# scaremin.net
KiCad netlist of a schematic drawn in EAGLE
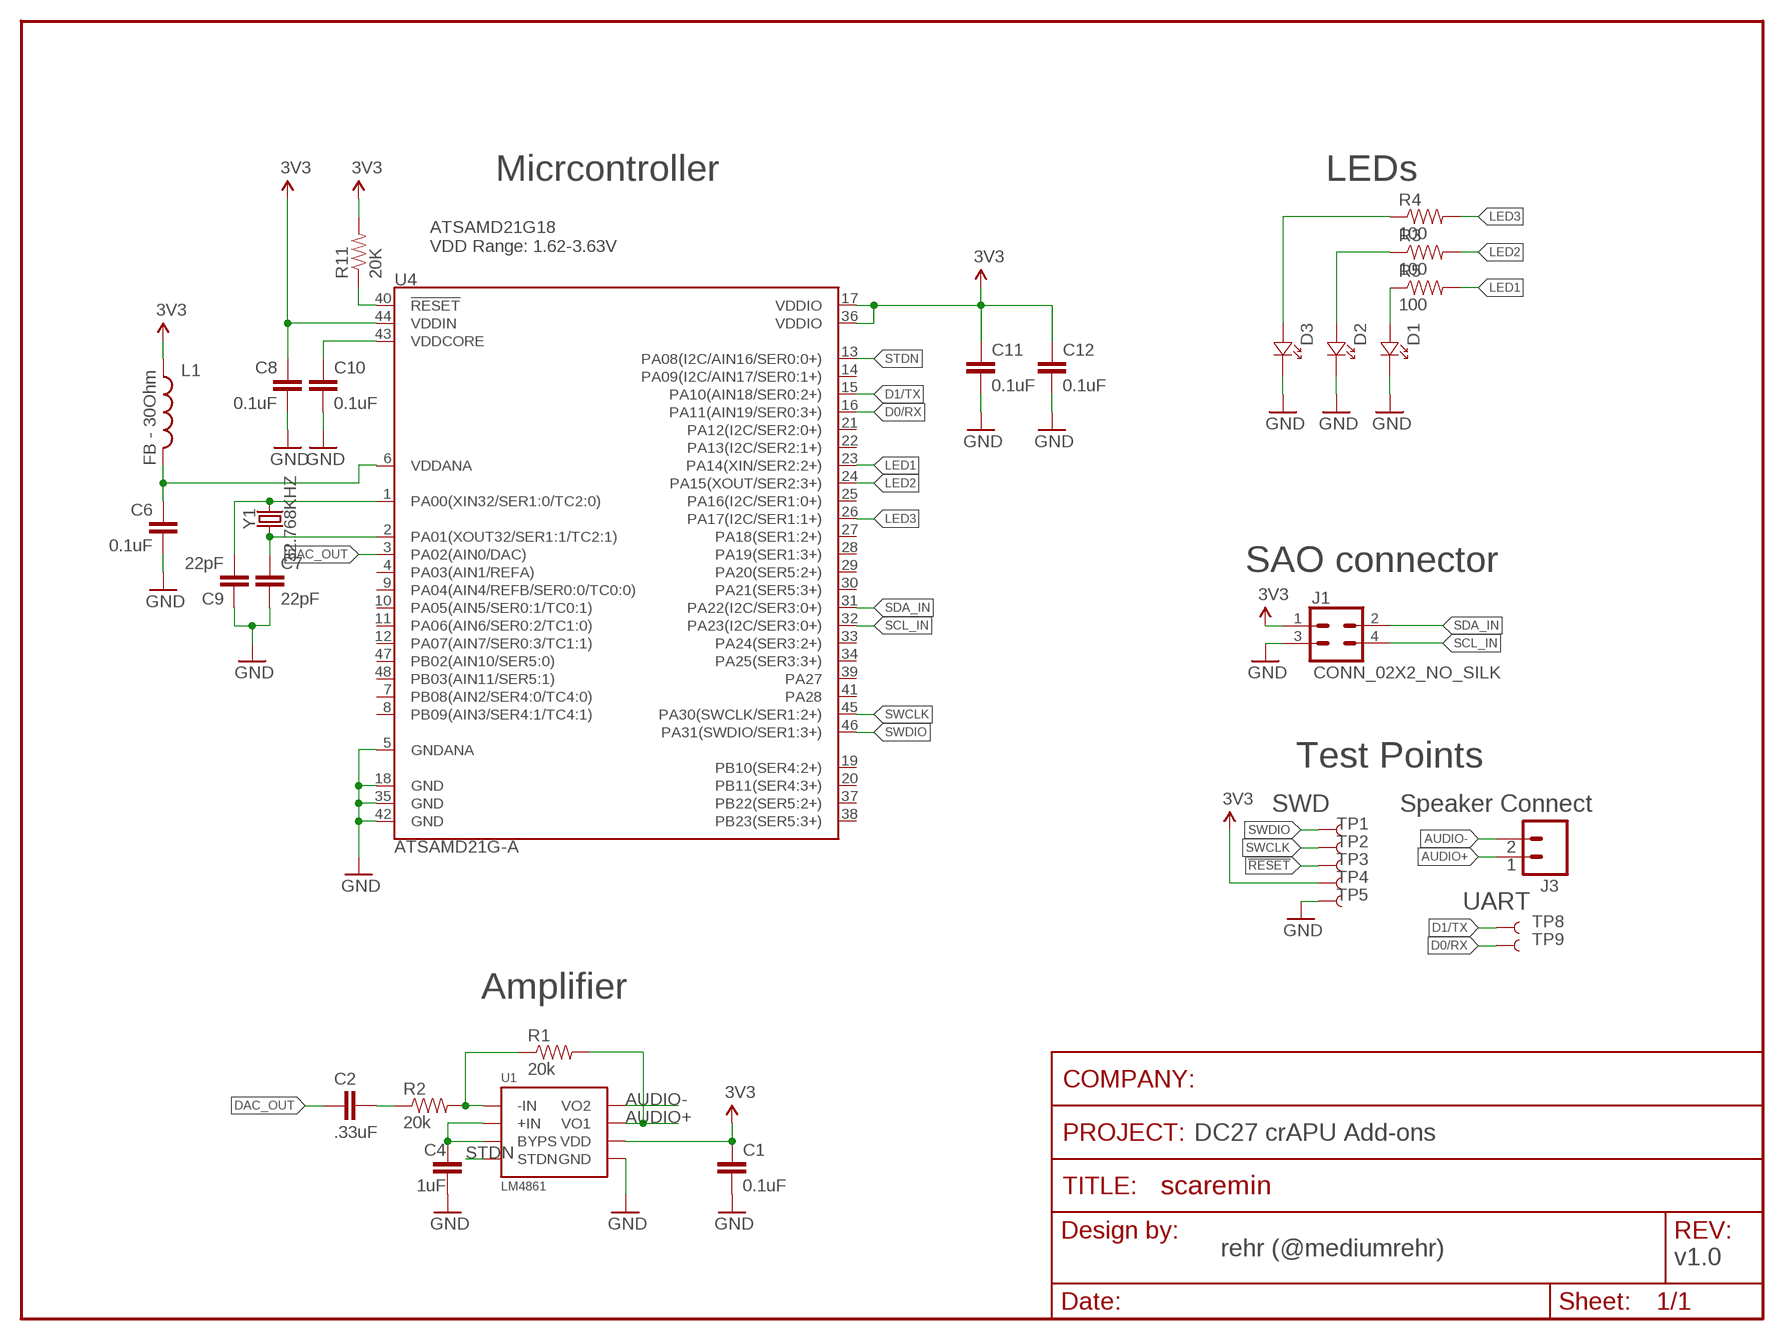
[diagram p0: schematic, sheet 1]

(export (version "E")
  (design (tool "Eeschema 10.0.6"))
  (components
    (comp (ref "C1")
      (value "0.1uF")
      (footprint "eagle-import:0603-CAP")
      (libsource (lib "eagle-import") (part "CAP0603-CAP"))
    )
    (comp (ref "C2")
      (value ".33uF")
      (footprint "eagle-import:0603-CAP")
      (libsource (lib "eagle-import") (part "CAP0603-CAP"))
    )
    (comp (ref "C4")
      (value "1uF")
      (footprint "eagle-import:0603-CAP")
      (libsource (lib "eagle-import") (part "CAP0603-CAP"))
    )
    (comp (ref "C6")
      (value "0.1uF")
      (footprint "eagle-import:0603-CAP")
      (libsource (lib "eagle-import") (part "0.1UF-25V(+80/-20%)(0603)"))
    )
    (comp (ref "C7")
      (value "22pF")
      (footprint "eagle-import:0603-CAP")
      (libsource (lib "eagle-import") (part "15PF-50V-5%(0603)"))
    )
    (comp (ref "C8")
      (value "0.1uF")
      (footprint "eagle-import:0603-CAP")
      (libsource (lib "eagle-import") (part "0.1UF-25V(+80/-20%)(0603)"))
    )
    (comp (ref "C9")
      (value "22pF")
      (footprint "eagle-import:0603-CAP")
      (libsource (lib "eagle-import") (part "15PF-50V-5%(0603)"))
    )
    (comp (ref "C10")
      (value "0.1uF")
      (footprint "eagle-import:0603-CAP")
      (libsource (lib "eagle-import") (part "0.1UF-25V(+80/-20%)(0603)"))
    )
    (comp (ref "C11")
      (value "0.1uF")
      (footprint "eagle-import:0603-CAP")
      (libsource (lib "eagle-import") (part "0.1UF-25V(+80/-20%)(0603)"))
    )
    (comp (ref "C12")
      (value "0.1uF")
      (footprint "eagle-import:0603-CAP")
      (libsource (lib "eagle-import") (part "0.1UF-25V(+80/-20%)(0603)"))
    )
    (comp (ref "D1")
      (value "LED1206REVERSE_NO_SILK")
      (footprint "eagle-import:1206_NO_SILK")
      (libsource (lib "eagle-import") (part "LED1206REVERSE_NO_SILK"))
    )
    (comp (ref "D2")
      (value "LED1206REVERSE_NO_SILK")
      (footprint "eagle-import:1206_NO_SILK")
      (libsource (lib "eagle-import") (part "LED1206REVERSE_NO_SILK"))
    )
    (comp (ref "D3")
      (value "LED1206REVERSE_NO_SILK")
      (footprint "eagle-import:1206_NO_SILK")
      (libsource (lib "eagle-import") (part "LED1206REVERSE_NO_SILK"))
    )
    (comp (ref "FRAME1")
      (value "FRAME-LETTER-BLANKNO_PACKAGE")
      (footprint "eagle-import:DUMMY")
      (fields (field (name "DESIGNER") "Nobody"))
      (libsource (lib "eagle-import") (part "FRAME-LETTER-BLANKNO_PACKAGE"))
    )
    (comp (ref "J1")
      (value "CONN_02X2_NO_SILK")
      (footprint "eagle-import:2X2_NO_SILK")
      (libsource (lib "eagle-import") (part "CONN_02X2_NO_SILK"))
    )
    (comp (ref "J3")
      (value "M02ROUND")
      (footprint "eagle-import:M02_ROUND")
      (libsource (lib "eagle-import") (part "M02ROUND"))
    )
    (comp (ref "L1")
      (value "FB - 30Ohm")
      (footprint "eagle-import:0603")
      (libsource (lib "eagle-import") (part "INDUCTOR0603"))
    )
    (comp (ref "R1")
      (value "20k")
      (footprint "eagle-import:0805")
      (libsource (lib "eagle-import") (part "RESISTOR0805-RES"))
    )
    (comp (ref "R2")
      (value "20k")
      (footprint "eagle-import:0805")
      (libsource (lib "eagle-import") (part "RESISTOR0805-RES"))
    )
    (comp (ref "R3")
      (value "100")
      (footprint "eagle-import:0603-RES")
      (libsource (lib "eagle-import") (part "10KOHM-1/10W-1%(0603)0603"))
    )
    (comp (ref "R4")
      (value "100")
      (footprint "eagle-import:0603-RES")
      (libsource (lib "eagle-import") (part "10KOHM-1/10W-1%(0603)0603"))
    )
    (comp (ref "R5")
      (value "100")
      (footprint "eagle-import:0603-RES")
      (libsource (lib "eagle-import") (part "10KOHM-1/10W-1%(0603)0603"))
    )
    (comp (ref "R11")
      (value "20K")
      (footprint "eagle-import:0603-RES")
      (libsource (lib "eagle-import") (part "10KOHM-1/10W-1%(0603)0603"))
    )
    (comp (ref "TP1")
      (value "TEST-POINT3X5")
      (footprint "eagle-import:PAD.03X.05")
      (libsource (lib "eagle-import") (part "TEST-POINT3X5"))
    )
    (comp (ref "TP2")
      (value "TEST-POINT3X5")
      (footprint "eagle-import:PAD.03X.05")
      (libsource (lib "eagle-import") (part "TEST-POINT3X5"))
    )
    (comp (ref "TP3")
      (value "TEST-POINT3X5")
      (footprint "eagle-import:PAD.03X.05")
      (libsource (lib "eagle-import") (part "TEST-POINT3X5"))
    )
    (comp (ref "TP4")
      (value "TEST-POINT3X5")
      (footprint "eagle-import:PAD.03X.05")
      (libsource (lib "eagle-import") (part "TEST-POINT3X5"))
    )
    (comp (ref "TP5")
      (value "TEST-POINT3X5")
      (footprint "eagle-import:PAD.03X.05")
      (libsource (lib "eagle-import") (part "TEST-POINT3X5"))
    )
    (comp (ref "TP8")
      (value "TEST-POINT3X4")
      (footprint "eagle-import:PAD.03X.04")
      (libsource (lib "eagle-import") (part "TEST-POINT3X4"))
    )
    (comp (ref "TP9")
      (value "TEST-POINT3X4")
      (footprint "eagle-import:PAD.03X.04")
      (libsource (lib "eagle-import") (part "TEST-POINT3X4"))
    )
    (comp (ref "U1")
      (value "LM4861")
      (footprint "eagle-import:8-SOIC")
      (libsource (lib "eagle-import") (part "LM4861"))
    )
    (comp (ref "U4")
      (value "ATSAMD21G-A")
      (footprint "eagle-import:TQFP-48")
      (libsource (lib "eagle-import") (part "ATSAMD21G-A"))
    )
    (comp (ref "Y1")
      (value "32.768KHZ")
      (footprint "eagle-import:ABS06")
      (libsource (lib "eagle-import") (part "ABS06-127-32.768KHZ"))
    )
  )
  (nets
    (net (code "1") (name "/~{RESET}") (class "Default")
      (node (ref "R11") (pin "1") (pinfunction "1_1") (pintype "passive"))
      (node (ref "TP3") (pin "P$1") (pinfunction "1_P$1") (pintype "bidirectional"))
      (node (ref "U4") (pin "40") (pinfunction "~{RESET}_40") (pintype "bidirectional"))
    )
    (net (code "2") (name "3V3") (class "Default")
      (node (ref "C1") (pin "1") (pinfunction "1_1") (pintype "passive"))
      (node (ref "C11") (pin "1") (pinfunction "1_1") (pintype "passive"))
      (node (ref "C12") (pin "1") (pinfunction "1_1") (pintype "passive"))
      (node (ref "C8") (pin "1") (pinfunction "1_1") (pintype "passive"))
      (node (ref "J1") (pin "1") (pinfunction "1_1") (pintype "bidirectional"))
      (node (ref "L1") (pin "1") (pinfunction "1_1") (pintype "passive"))
      (node (ref "R11") (pin "2") (pinfunction "2_2") (pintype "passive"))
      (node (ref "TP4") (pin "P$1") (pinfunction "1_P$1") (pintype "bidirectional"))
      (node (ref "U1") (pin "P$6") (pinfunction "VDD_P$6") (pintype "bidirectional"))
      (node (ref "U4") (pin "17") (pinfunction "VDDIO_17") (pintype "bidirectional"))
      (node (ref "U4") (pin "36") (pinfunction "VDDIO_36") (pintype "bidirectional"))
      (node (ref "U4") (pin "44") (pinfunction "VDDIN_44") (pintype "bidirectional"))
    )
    (net (code "3") (name "AUDIO+") (class "Default")
      (node (ref "J3") (pin "P$1") (pinfunction "P$1_P$1") (pintype "bidirectional"))
      (node (ref "R1") (pin "2") (pinfunction "2_2") (pintype "passive"))
      (node (ref "U1") (pin "P$5") (pinfunction "VO1_P$5") (pintype "bidirectional"))
    )
    (net (code "4") (name "AUDIO-") (class "Default")
      (node (ref "J3") (pin "P$2") (pinfunction "P$2_P$2") (pintype "bidirectional"))
      (node (ref "U1") (pin "P$8") (pinfunction "VO2_P$8") (pintype "bidirectional"))
    )
    (net (code "5") (name "D0{slash}RX") (class "Default")
      (node (ref "TP9") (pin "P$1") (pinfunction "1_P$1") (pintype "bidirectional"))
      (node (ref "U4") (pin "16") (pinfunction "PA11(AIN19/SER0:3+)_16") (pintype "bidirectional"))
    )
    (net (code "6") (name "D1{slash}TX") (class "Default")
      (node (ref "TP8") (pin "P$1") (pinfunction "1_P$1") (pintype "bidirectional"))
      (node (ref "U4") (pin "15") (pinfunction "PA10(AIN18/SER0:2+)_15") (pintype "bidirectional"))
    )
    (net (code "7") (name "DAC_OUT") (class "Default")
      (node (ref "C2") (pin "2") (pinfunction "2_2") (pintype "passive"))
      (node (ref "U4") (pin "3") (pinfunction "PA02(AIN0/DAC)_3") (pintype "bidirectional"))
    )
    (net (code "8") (name "GND") (class "Default")
      (node (ref "C1") (pin "2") (pinfunction "2_2") (pintype "passive"))
      (node (ref "C10") (pin "2") (pinfunction "2_2") (pintype "passive"))
      (node (ref "C11") (pin "2") (pinfunction "2_2") (pintype "passive"))
      (node (ref "C12") (pin "2") (pinfunction "2_2") (pintype "passive"))
      (node (ref "C4") (pin "2") (pinfunction "2_2") (pintype "passive"))
      (node (ref "C6") (pin "2") (pinfunction "2_2") (pintype "passive"))
      (node (ref "C7") (pin "2") (pinfunction "2_2") (pintype "passive"))
      (node (ref "C8") (pin "2") (pinfunction "2_2") (pintype "passive"))
      (node (ref "C9") (pin "1") (pinfunction "1_1") (pintype "passive"))
      (node (ref "D1") (pin "P$1") (pinfunction "P$2_P$1") (pintype "bidirectional"))
      (node (ref "D2") (pin "P$1") (pinfunction "P$2_P$1") (pintype "bidirectional"))
      (node (ref "D3") (pin "P$1") (pinfunction "P$2_P$1") (pintype "bidirectional"))
      (node (ref "J1") (pin "3") (pinfunction "3_3") (pintype "bidirectional"))
      (node (ref "TP5") (pin "P$1") (pinfunction "1_P$1") (pintype "bidirectional"))
      (node (ref "U1") (pin "P$7") (pinfunction "GND_P$7") (pintype "bidirectional"))
      (node (ref "U4") (pin "18") (pinfunction "GND_18") (pintype "bidirectional"))
      (node (ref "U4") (pin "35") (pinfunction "GND_35") (pintype "bidirectional"))
      (node (ref "U4") (pin "42") (pinfunction "GND_42") (pintype "bidirectional"))
      (node (ref "U4") (pin "5") (pinfunction "GNDANA_5") (pintype "bidirectional"))
    )
    (net (code "9") (name "LED1") (class "Default")
      (node (ref "R5") (pin "2") (pinfunction "2_2") (pintype "passive"))
      (node (ref "U4") (pin "23") (pinfunction "PA14(XIN/SER2:2+)_23") (pintype "bidirectional"))
    )
    (net (code "10") (name "LED2") (class "Default")
      (node (ref "R3") (pin "2") (pinfunction "2_2") (pintype "passive"))
      (node (ref "U4") (pin "24") (pinfunction "PA15(XOUT/SER2:3+)_24") (pintype "bidirectional"))
    )
    (net (code "11") (name "LED3") (class "Default")
      (node (ref "R4") (pin "2") (pinfunction "2_2") (pintype "passive"))
      (node (ref "U4") (pin "26") (pinfunction "PA17(I2C/SER1:1+)_26") (pintype "bidirectional"))
    )
    (net (code "12") (name "Net-(C2-Pad1)") (class "Default")
      (node (ref "C2") (pin "1") (pinfunction "1_1") (pintype "passive"))
      (node (ref "R2") (pin "1") (pinfunction "1_1") (pintype "passive"))
    )
    (net (code "13") (name "Net-(D1-P$1)") (class "Default")
      (node (ref "D1") (pin "P$2") (pinfunction "P$1_P$2") (pintype "bidirectional"))
      (node (ref "R5") (pin "1") (pinfunction "1_1") (pintype "passive"))
    )
    (net (code "14") (name "Net-(D2-P$1)") (class "Default")
      (node (ref "D2") (pin "P$2") (pinfunction "P$1_P$2") (pintype "bidirectional"))
      (node (ref "R3") (pin "1") (pinfunction "1_1") (pintype "passive"))
    )
    (net (code "15") (name "Net-(D3-P$1)") (class "Default")
      (node (ref "D3") (pin "P$2") (pinfunction "P$1_P$2") (pintype "bidirectional"))
      (node (ref "R4") (pin "1") (pinfunction "1_1") (pintype "passive"))
    )
    (net (code "16") (name "Net-(U1-+IN)") (class "Default")
      (node (ref "C4") (pin "1") (pinfunction "1_1") (pintype "passive"))
      (node (ref "U1") (pin "P$2") (pinfunction "BYPS_P$2") (pintype "bidirectional"))
      (node (ref "U1") (pin "P$3") (pinfunction "+IN_P$3") (pintype "bidirectional"))
    )
    (net (code "17") (name "Net-(U1--IN)") (class "Default")
      (node (ref "R1") (pin "1") (pinfunction "1_1") (pintype "passive"))
      (node (ref "R2") (pin "2") (pinfunction "2_2") (pintype "passive"))
      (node (ref "U1") (pin "P$4") (pinfunction "-IN_P$4") (pintype "bidirectional"))
    )
    (net (code "18") (name "Net-(U4-PA00(XIN32{slash}SER1:0{slash}TC2:0))") (class "Default")
      (node (ref "C9") (pin "2") (pinfunction "2_2") (pintype "passive"))
      (node (ref "U4") (pin "1") (pinfunction "PA00(XIN32/SER1:0/TC2:0)_1") (pintype "bidirectional"))
      (node (ref "Y1") (pin "P$2") (pinfunction "2_P$2") (pintype "passive"))
    )
    (net (code "19") (name "Net-(U4-PA01(XOUT32{slash}SER1:1{slash}TC2:1))") (class "Default")
      (node (ref "C7") (pin "1") (pinfunction "1_1") (pintype "passive"))
      (node (ref "U4") (pin "2") (pinfunction "PA01(XOUT32/SER1:1/TC2:1)_2") (pintype "bidirectional"))
      (node (ref "Y1") (pin "P$1") (pinfunction "1_P$1") (pintype "passive"))
    )
    (net (code "20") (name "Net-(U4-VDDANA)") (class "Default")
      (node (ref "C6") (pin "1") (pinfunction "1_1") (pintype "passive"))
      (node (ref "L1") (pin "2") (pinfunction "2_2") (pintype "passive"))
      (node (ref "U4") (pin "6") (pinfunction "VDDANA_6") (pintype "bidirectional"))
    )
    (net (code "21") (name "Net-(U4-VDDCORE)") (class "Default")
      (node (ref "C10") (pin "1") (pinfunction "1_1") (pintype "passive"))
      (node (ref "U4") (pin "43") (pinfunction "VDDCORE_43") (pintype "bidirectional"))
    )
    (net (code "22") (name "SCL_IN") (class "Default")
      (node (ref "J1") (pin "4") (pinfunction "4_4") (pintype "bidirectional"))
      (node (ref "U4") (pin "32") (pinfunction "PA23(I2C/SER3:0+)_32") (pintype "bidirectional"))
    )
    (net (code "23") (name "SDA_IN") (class "Default")
      (node (ref "J1") (pin "2") (pinfunction "2_2") (pintype "bidirectional"))
      (node (ref "U4") (pin "31") (pinfunction "PA22(I2C/SER3:0+)_31") (pintype "bidirectional"))
    )
    (net (code "24") (name "STDN") (class "Default")
      (node (ref "U1") (pin "P$1") (pinfunction "STDN_P$1") (pintype "bidirectional"))
      (node (ref "U4") (pin "13") (pinfunction "PA08(I2C/AIN16/SER0:0+)_13") (pintype "bidirectional"))
    )
    (net (code "25") (name "SWCLK") (class "Default")
      (node (ref "TP2") (pin "P$1") (pinfunction "1_P$1") (pintype "bidirectional"))
      (node (ref "U4") (pin "45") (pinfunction "PA30(SWCLK/SER1:2+)_45") (pintype "bidirectional"))
    )
    (net (code "26") (name "SWDIO") (class "Default")
      (node (ref "TP1") (pin "P$1") (pinfunction "1_P$1") (pintype "bidirectional"))
      (node (ref "U4") (pin "46") (pinfunction "PA31(SWDIO/SER1:3+)_46") (pintype "bidirectional"))
    )
    (net (code "27") (name "unconnected-(U4-PA03(AIN1{slash}REFA)-Pad4)") (class "Default")
      (node (ref "U4") (pin "4") (pinfunction "PA03(AIN1/REFA)_4") (pintype "bidirectional"))
    )
    (net (code "28") (name "unconnected-(U4-PA04(AIN4{slash}REFB{slash}SER0:0{slash}TC0:0)-Pad9)") (class "Default")
      (node (ref "U4") (pin "9") (pinfunction "PA04(AIN4/REFB/SER0:0/TC0:0)_9") (pintype "bidirectional"))
    )
    (net (code "29") (name "unconnected-(U4-PA05(AIN5{slash}SER0:1{slash}TC0:1)-Pad10)") (class "Default")
      (node (ref "U4") (pin "10") (pinfunction "PA05(AIN5/SER0:1/TC0:1)_10") (pintype "bidirectional"))
    )
    (net (code "30") (name "unconnected-(U4-PA06(AIN6{slash}SER0:2{slash}TC1:0)-Pad11)") (class "Default")
      (node (ref "U4") (pin "11") (pinfunction "PA06(AIN6/SER0:2/TC1:0)_11") (pintype "bidirectional"))
    )
    (net (code "31") (name "unconnected-(U4-PA07(AIN7{slash}SER0:3{slash}TC1:1)-Pad12)") (class "Default")
      (node (ref "U4") (pin "12") (pinfunction "PA07(AIN7/SER0:3/TC1:1)_12") (pintype "bidirectional"))
    )
    (net (code "32") (name "unconnected-(U4-PA09(I2C{slash}AIN17{slash}SER0:1+)-Pad14)") (class "Default")
      (node (ref "U4") (pin "14") (pinfunction "PA09(I2C/AIN17/SER0:1+)_14") (pintype "bidirectional"))
    )
    (net (code "33") (name "unconnected-(U4-PA12(I2C{slash}SER2:0+)-Pad21)") (class "Default")
      (node (ref "U4") (pin "21") (pinfunction "PA12(I2C/SER2:0+)_21") (pintype "bidirectional"))
    )
    (net (code "34") (name "unconnected-(U4-PA13(I2C{slash}SER2:1+)-Pad22)") (class "Default")
      (node (ref "U4") (pin "22") (pinfunction "PA13(I2C/SER2:1+)_22") (pintype "bidirectional"))
    )
    (net (code "35") (name "unconnected-(U4-PA16(I2C{slash}SER1:0+)-Pad25)") (class "Default")
      (node (ref "U4") (pin "25") (pinfunction "PA16(I2C/SER1:0+)_25") (pintype "bidirectional"))
    )
    (net (code "36") (name "unconnected-(U4-PA18(SER1:2+)-Pad27)") (class "Default")
      (node (ref "U4") (pin "27") (pinfunction "PA18(SER1:2+)_27") (pintype "bidirectional"))
    )
    (net (code "37") (name "unconnected-(U4-PA19(SER1:3+)-Pad28)") (class "Default")
      (node (ref "U4") (pin "28") (pinfunction "PA19(SER1:3+)_28") (pintype "bidirectional"))
    )
    (net (code "38") (name "unconnected-(U4-PA20(SER5:2+)-Pad29)") (class "Default")
      (node (ref "U4") (pin "29") (pinfunction "PA20(SER5:2+)_29") (pintype "bidirectional"))
    )
    (net (code "39") (name "unconnected-(U4-PA21(SER5:3+)-Pad30)") (class "Default")
      (node (ref "U4") (pin "30") (pinfunction "PA21(SER5:3+)_30") (pintype "bidirectional"))
    )
    (net (code "40") (name "unconnected-(U4-PA24(SER3:2+)-Pad33)") (class "Default")
      (node (ref "U4") (pin "33") (pinfunction "PA24(SER3:2+)_33") (pintype "bidirectional"))
    )
    (net (code "41") (name "unconnected-(U4-PA25(SER3:3+)-Pad34)") (class "Default")
      (node (ref "U4") (pin "34") (pinfunction "PA25(SER3:3+)_34") (pintype "bidirectional"))
    )
    (net (code "42") (name "unconnected-(U4-PA27-Pad39)") (class "Default")
      (node (ref "U4") (pin "39") (pinfunction "PA27_39") (pintype "bidirectional"))
    )
    (net (code "43") (name "unconnected-(U4-PA28-Pad41)") (class "Default")
      (node (ref "U4") (pin "41") (pinfunction "PA28_41") (pintype "bidirectional"))
    )
    (net (code "44") (name "unconnected-(U4-PB02(AIN10{slash}SER5:0)-Pad47)") (class "Default")
      (node (ref "U4") (pin "47") (pinfunction "PB02(AIN10/SER5:0)_47") (pintype "bidirectional"))
    )
    (net (code "45") (name "unconnected-(U4-PB03(AIN11{slash}SER5:1)-Pad48)") (class "Default")
      (node (ref "U4") (pin "48") (pinfunction "PB03(AIN11/SER5:1)_48") (pintype "bidirectional"))
    )
    (net (code "46") (name "unconnected-(U4-PB08(AIN2{slash}SER4:0{slash}TC4:0)-Pad7)") (class "Default")
      (node (ref "U4") (pin "7") (pinfunction "PB08(AIN2/SER4:0/TC4:0)_7") (pintype "bidirectional"))
    )
    (net (code "47") (name "unconnected-(U4-PB09(AIN3{slash}SER4:1{slash}TC4:1)-Pad8)") (class "Default")
      (node (ref "U4") (pin "8") (pinfunction "PB09(AIN3/SER4:1/TC4:1)_8") (pintype "bidirectional"))
    )
    (net (code "48") (name "unconnected-(U4-PB10(SER4:2+)-Pad19)") (class "Default")
      (node (ref "U4") (pin "19") (pinfunction "PB10(SER4:2+)_19") (pintype "bidirectional"))
    )
    (net (code "49") (name "unconnected-(U4-PB11(SER4:3+)-Pad20)") (class "Default")
      (node (ref "U4") (pin "20") (pinfunction "PB11(SER4:3+)_20") (pintype "bidirectional"))
    )
    (net (code "50") (name "unconnected-(U4-PB22(SER5:2+)-Pad37)") (class "Default")
      (node (ref "U4") (pin "37") (pinfunction "PB22(SER5:2+)_37") (pintype "bidirectional"))
    )
    (net (code "51") (name "unconnected-(U4-PB23(SER5:3+)-Pad38)") (class "Default")
      (node (ref "U4") (pin "38") (pinfunction "PB23(SER5:3+)_38") (pintype "bidirectional"))
    )
  )
)
